# V1_0.net
KiCad netlist of a schematic drawn in EasyEDA Pro
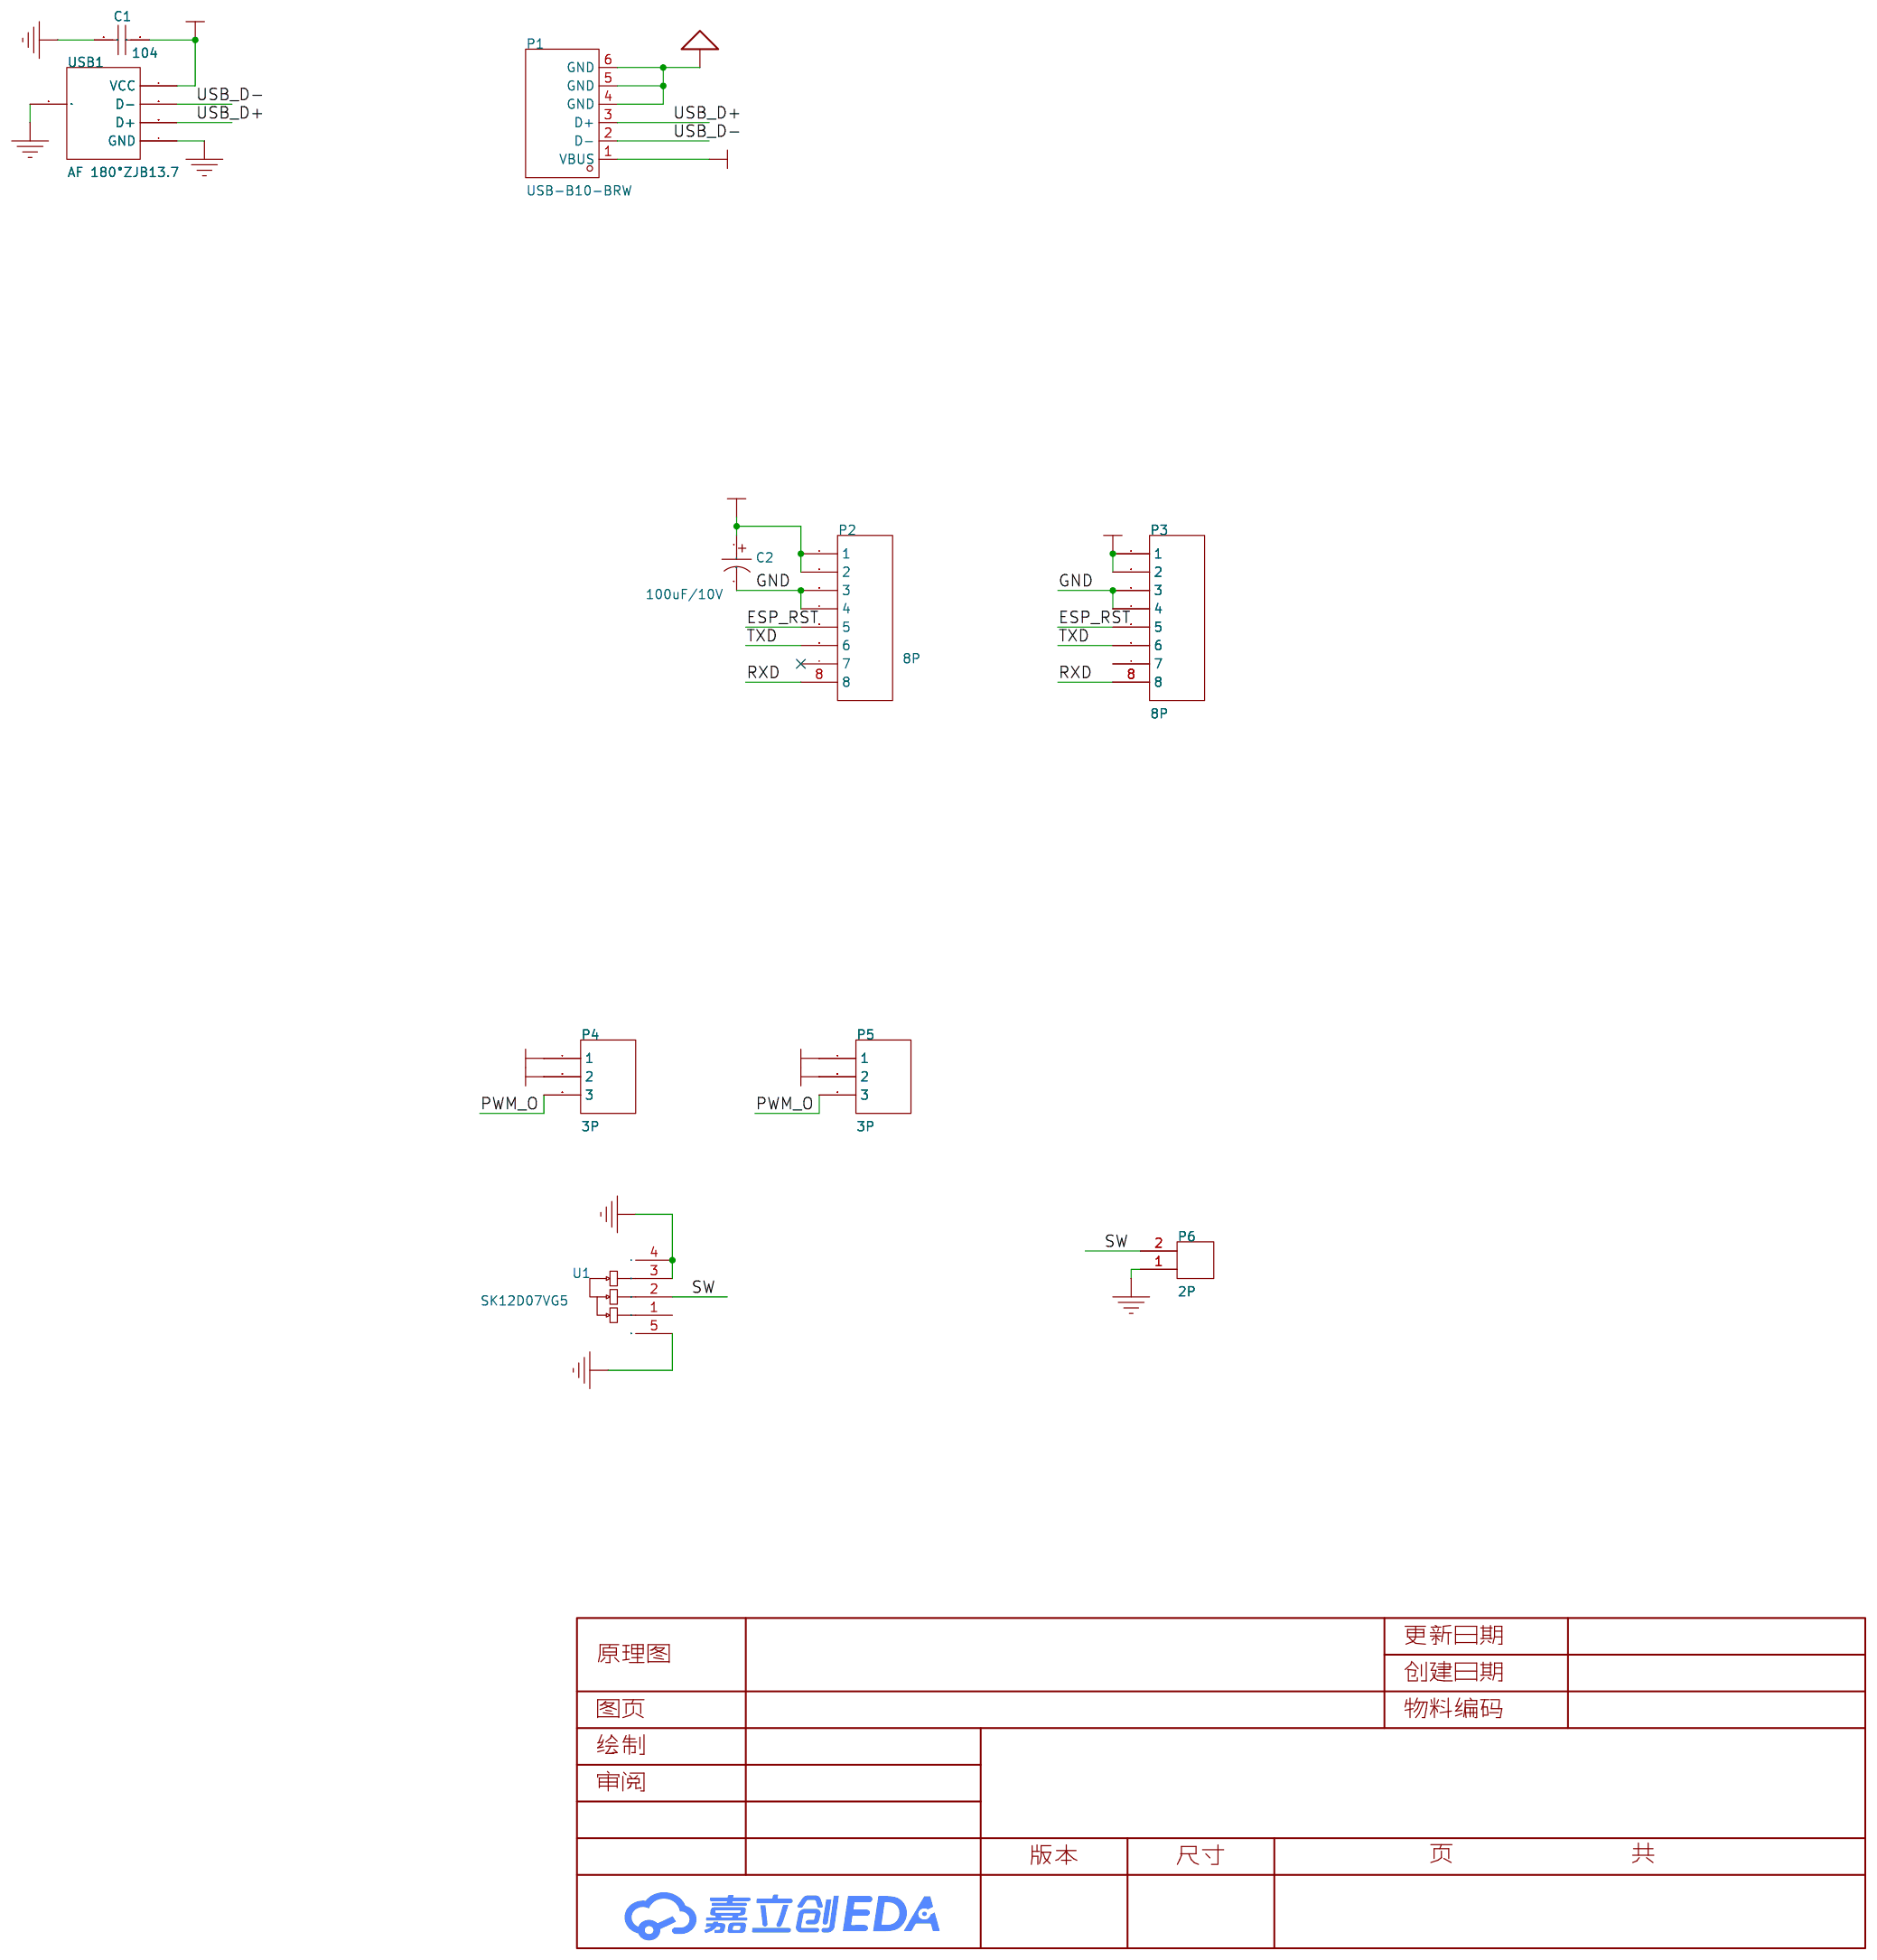
[diagram p0: schematic sheet]

(export (version "E")
  (design (tool "Eeschema 10.0.6"))
  (components
    (comp (ref "C1")
      (value "104")
      (footprint "easyedapro:0603C")
      (description "Capacitor (Semiconductor SIM Model)")
      (libsource (lib "easyedapro") (part "Cap Semi"))
    )
    (comp (ref "C2")
      (value "100uF/10V")
      (footprint "easyedapro:CAP-SMD_BD5.0-L5.3-W5.3-RD")
      (fields (field (name "Manufacturer Part") "CS1A101M-CRD54") (field (name "Manufacturer") "ST(先科)"))
      (libsource (lib "easyedapro") (part "CS1A101M-CRD54"))
    )
    (comp (ref "P1")
      (value "USB-B10-BRW")
      (footprint "easyedapro:USB-B-TH_USB-B10-BRW")
      (fields (field (name "Manufacturer") "XUNPU(讯普)"))
      (libsource (lib "easyedapro") (part "USB-B10-BRW"))
    )
    (comp (ref "P2") (value "8P") (footprint "easyedapro:IDC8") (libsource (lib "easyedapro") (part "8P")))
    (comp (ref "P3") (value "8P") (footprint "easyedapro:IDC8弯脚") (libsource (lib "easyedapro") (part "8P")))
    (comp (ref "P4")
      (value "3P")
      (footprint "easyedapro:HDR1X3_CON")
      (libsource (lib "easyedapro") (part "3P"))
    )
    (comp (ref "P5")
      (value "3P")
      (footprint "easyedapro:HDR1X3_P")
      (libsource (lib "easyedapro") (part "3P"))
    )
    (comp (ref "P6") (value "2P") (libsource (lib "easyedapro") (part "2P")))
    (comp (ref "U1")
      (value "SK12D07VG5")
      (footprint "easyedapro:SW-TH_SHOU_SK12D07VG5")
      (description "电路结构:单刀双掷;安装方式:-;开关颜色:-;额定电流:500mA;额定电压:50V;工作寿命:5千次;")
      (fields (field (name "Manufacturer") "SHOU HAN(首韩)"))
      (libsource (lib "easyedapro") (part "SK12D07VG5_C3020419"))
    )
    (comp (ref "USB1")
      (value "AF 180°ZJB13.7")
      (footprint "easyedapro:USB-A-TH_AF-ZJB13.7")
      (description "连接器类型:Type-A;标准:USB 2.0;公母:母;安装方式:直插;触点数量:4P;端口数量:1;额定电流 - 电源:1.5A;工作温度范围:-25°C~+85°C;")
      (fields (field (name "Manufacturer") "SHOU HAN(首韩)"))
      (libsource (lib "easyedapro") (part "AF 180°ZJB13.7"))
    )
  )
  (nets
    (net (code "1") (name "/ESP_RST") (class "Default")
      (node (ref "P2") (pin "5") (pinfunction "5_5") (pintype "unspecified"))
      (node (ref "P3") (pin "5") (pinfunction "5_5") (pintype "unspecified"))
    )
    (net (code "2") (name "/PWM_O") (class "Default")
      (node (ref "P4") (pin "3") (pinfunction "3_3") (pintype "unspecified"))
      (node (ref "P5") (pin "3") (pinfunction "3_3") (pintype "unspecified"))
    )
    (net (code "3") (name "/RXD") (class "Default")
      (node (ref "P2") (pin "8") (pinfunction "8_8") (pintype "unspecified"))
      (node (ref "P3") (pin "8") (pinfunction "8_8") (pintype "unspecified"))
    )
    (net (code "4") (name "/SW") (class "Default")
      (node (ref "P6") (pin "2") (pintype "input"))
      (node (ref "U1") (pin "2") (pinfunction "2_2") (pintype "unspecified"))
    )
    (net (code "5") (name "/TXD") (class "Default")
      (node (ref "P2") (pin "6") (pinfunction "6_6") (pintype "unspecified"))
      (node (ref "P3") (pin "6") (pinfunction "6_6") (pintype "unspecified"))
    )
    (net (code "6") (name "/USB_D+") (class "Default")
      (node (ref "P1") (pin "3") (pinfunction "D+_3") (pintype "unspecified"))
      (node (ref "USB1") (pin "3") (pinfunction "D+_3") (pintype "input"))
    )
    (net (code "7") (name "/USB_D-") (class "Default")
      (node (ref "P1") (pin "2") (pinfunction "D-_2") (pintype "unspecified"))
      (node (ref "USB1") (pin "2") (pinfunction "D-_2") (pintype "input"))
    )
    (net (code "8") (name "5V_VCC") (class "Default")
      (node (ref "C2") (pin "1") (pinfunction "1_1") (pintype "input"))
      (node (ref "P2") (pin "1") (pinfunction "1_1") (pintype "unspecified"))
      (node (ref "P2") (pin "2") (pinfunction "2_2") (pintype "unspecified"))
      (node (ref "P3") (pin "1") (pinfunction "1_1") (pintype "unspecified"))
      (node (ref "P3") (pin "2") (pinfunction "2_2") (pintype "unspecified"))
    )
    (net (code "9") (name "24V") (class "Default")
      (node (ref "P4") (pin "1") (pinfunction "1_1") (pintype "unspecified"))
      (node (ref "P5") (pin "1") (pinfunction "1_1") (pintype "unspecified"))
    )
    (net (code "10") (name "GND") (class "Default")
      (node (ref "C1") (pin "2") (pinfunction "2_2") (pintype "unspecified"))
      (node (ref "C2") (pin "2") (pinfunction "2_2") (pintype "input"))
      (node (ref "P1") (pin "4") (pinfunction "GND_4") (pintype "unspecified"))
      (node (ref "P1") (pin "5") (pinfunction "GND_5") (pintype "unspecified"))
      (node (ref "P1") (pin "6") (pinfunction "GND_6") (pintype "unspecified"))
      (node (ref "P2") (pin "3") (pinfunction "3_3") (pintype "unspecified"))
      (node (ref "P2") (pin "4") (pinfunction "4_4") (pintype "unspecified"))
      (node (ref "P3") (pin "3") (pinfunction "3_3") (pintype "unspecified"))
      (node (ref "P3") (pin "4") (pinfunction "4_4") (pintype "unspecified"))
      (node (ref "P4") (pin "2") (pinfunction "2_2") (pintype "unspecified"))
      (node (ref "P5") (pin "2") (pinfunction "2_2") (pintype "unspecified"))
      (node (ref "P6") (pin "1") (pintype "input"))
      (node (ref "U1") (pin "3") (pinfunction "3_3") (pintype "unspecified"))
      (node (ref "U1") (pin "4") (pinfunction "4_4") (pintype "unspecified"))
      (node (ref "U1") (pin "5") (pinfunction "5_5") (pintype "unspecified"))
      (node (ref "USB1") (pin "4") (pinfunction "GND_4") (pintype "input"))
      (node (ref "USB1") (pin "5") (pinfunction "SHLD_5") (pintype "unspecified"))
    )
    (net (code "11") (name "VUSB") (class "Default")
      (node (ref "C1") (pin "1") (pinfunction "1_1") (pintype "unspecified"))
      (node (ref "P1") (pin "1") (pinfunction "VBUS_1") (pintype "unspecified"))
      (node (ref "USB1") (pin "1") (pinfunction "VCC_1") (pintype "input"))
    )
    (net (code "12") (name "unconnected-(P2-Pad7)") (class "Default")
      (node (ref "P2") (pin "7") (pinfunction "7_7") (pintype "unspecified+no_connect"))
    )
    (net (code "13") (name "unconnected-(P3-Pad7)") (class "Default")
      (node (ref "P3") (pin "7") (pinfunction "7_7") (pintype "unspecified"))
    )
    (net (code "14") (name "unconnected-(U1-Pad1)") (class "Default")
      (node (ref "U1") (pin "1") (pinfunction "1_1") (pintype "unspecified"))
    )
  )
)
